# Ambient_Board_v1_1b.net
KiCad netlist of a schematic drawn in EAGLE
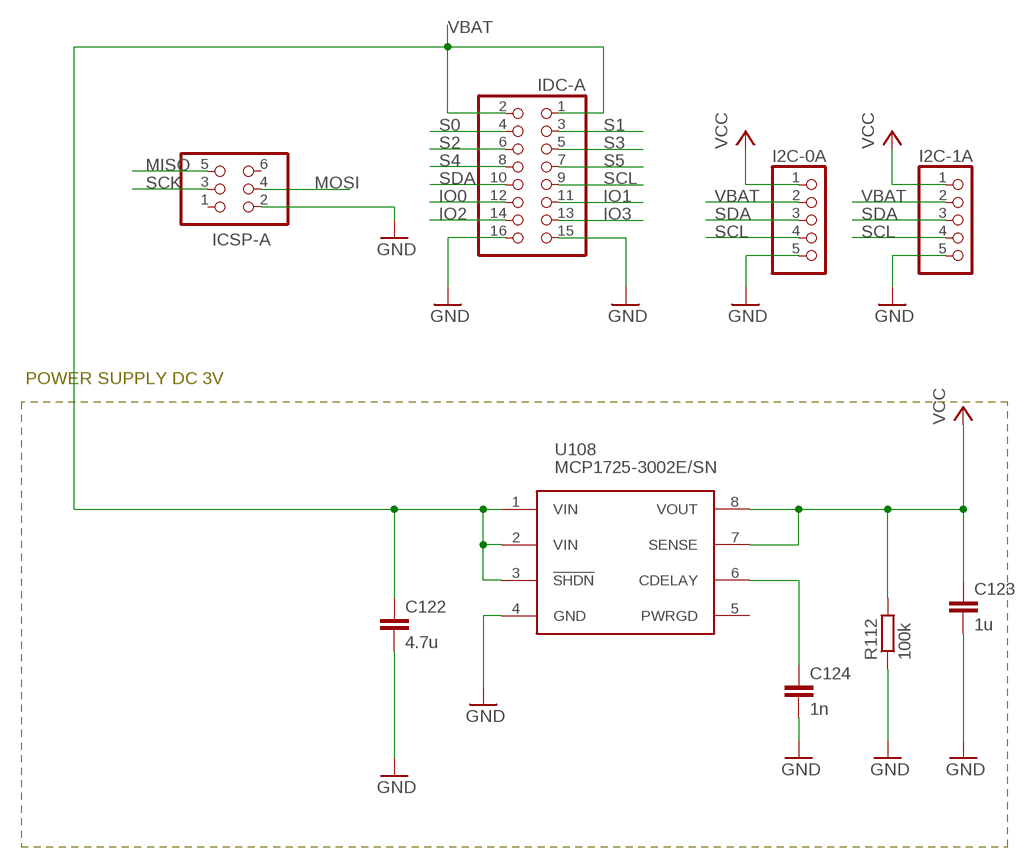
[diagram p0: schematic, sheet 1]
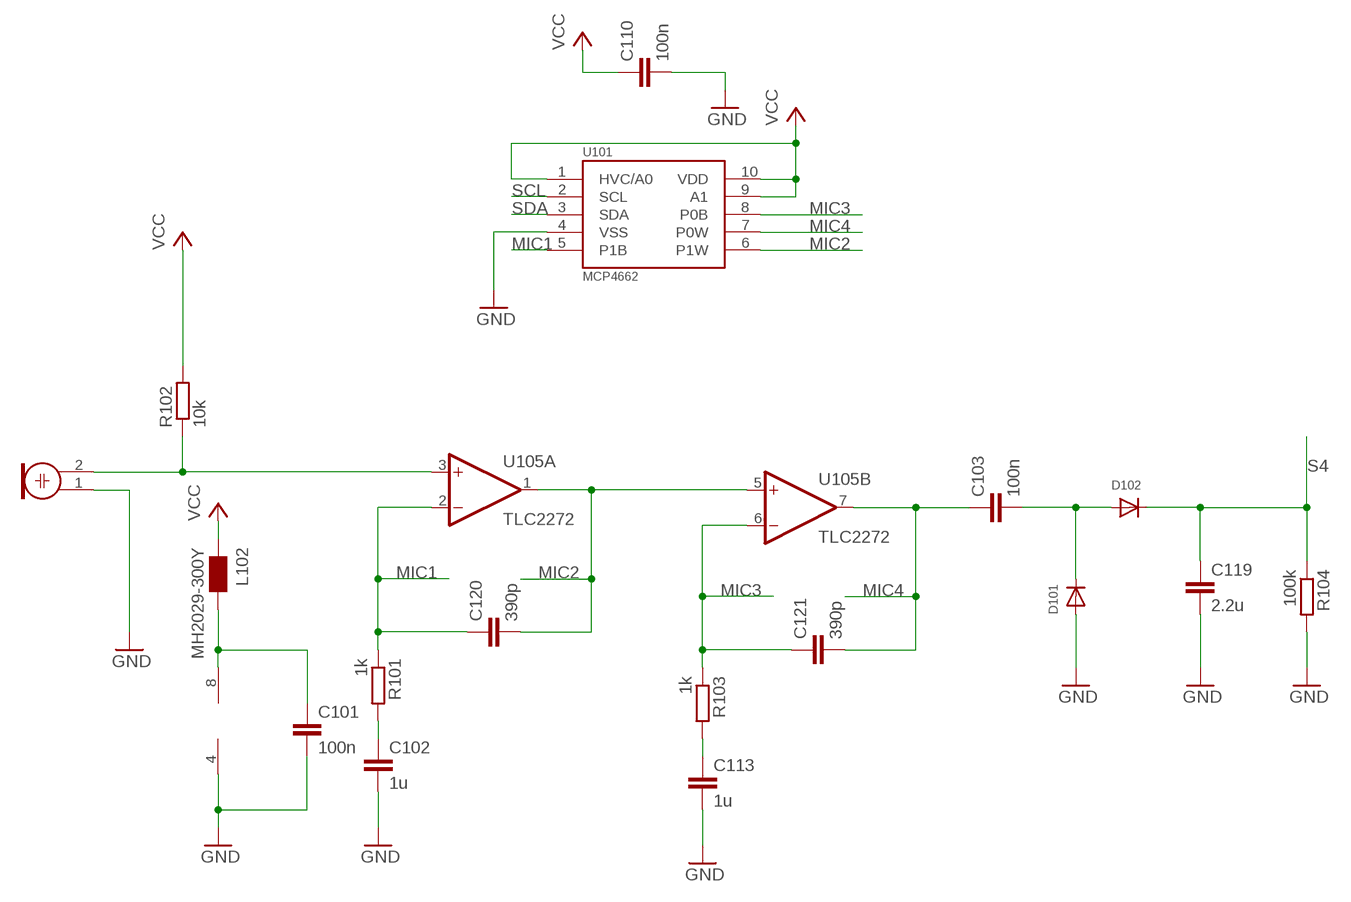
[diagram p1: schematic, sheet 2]
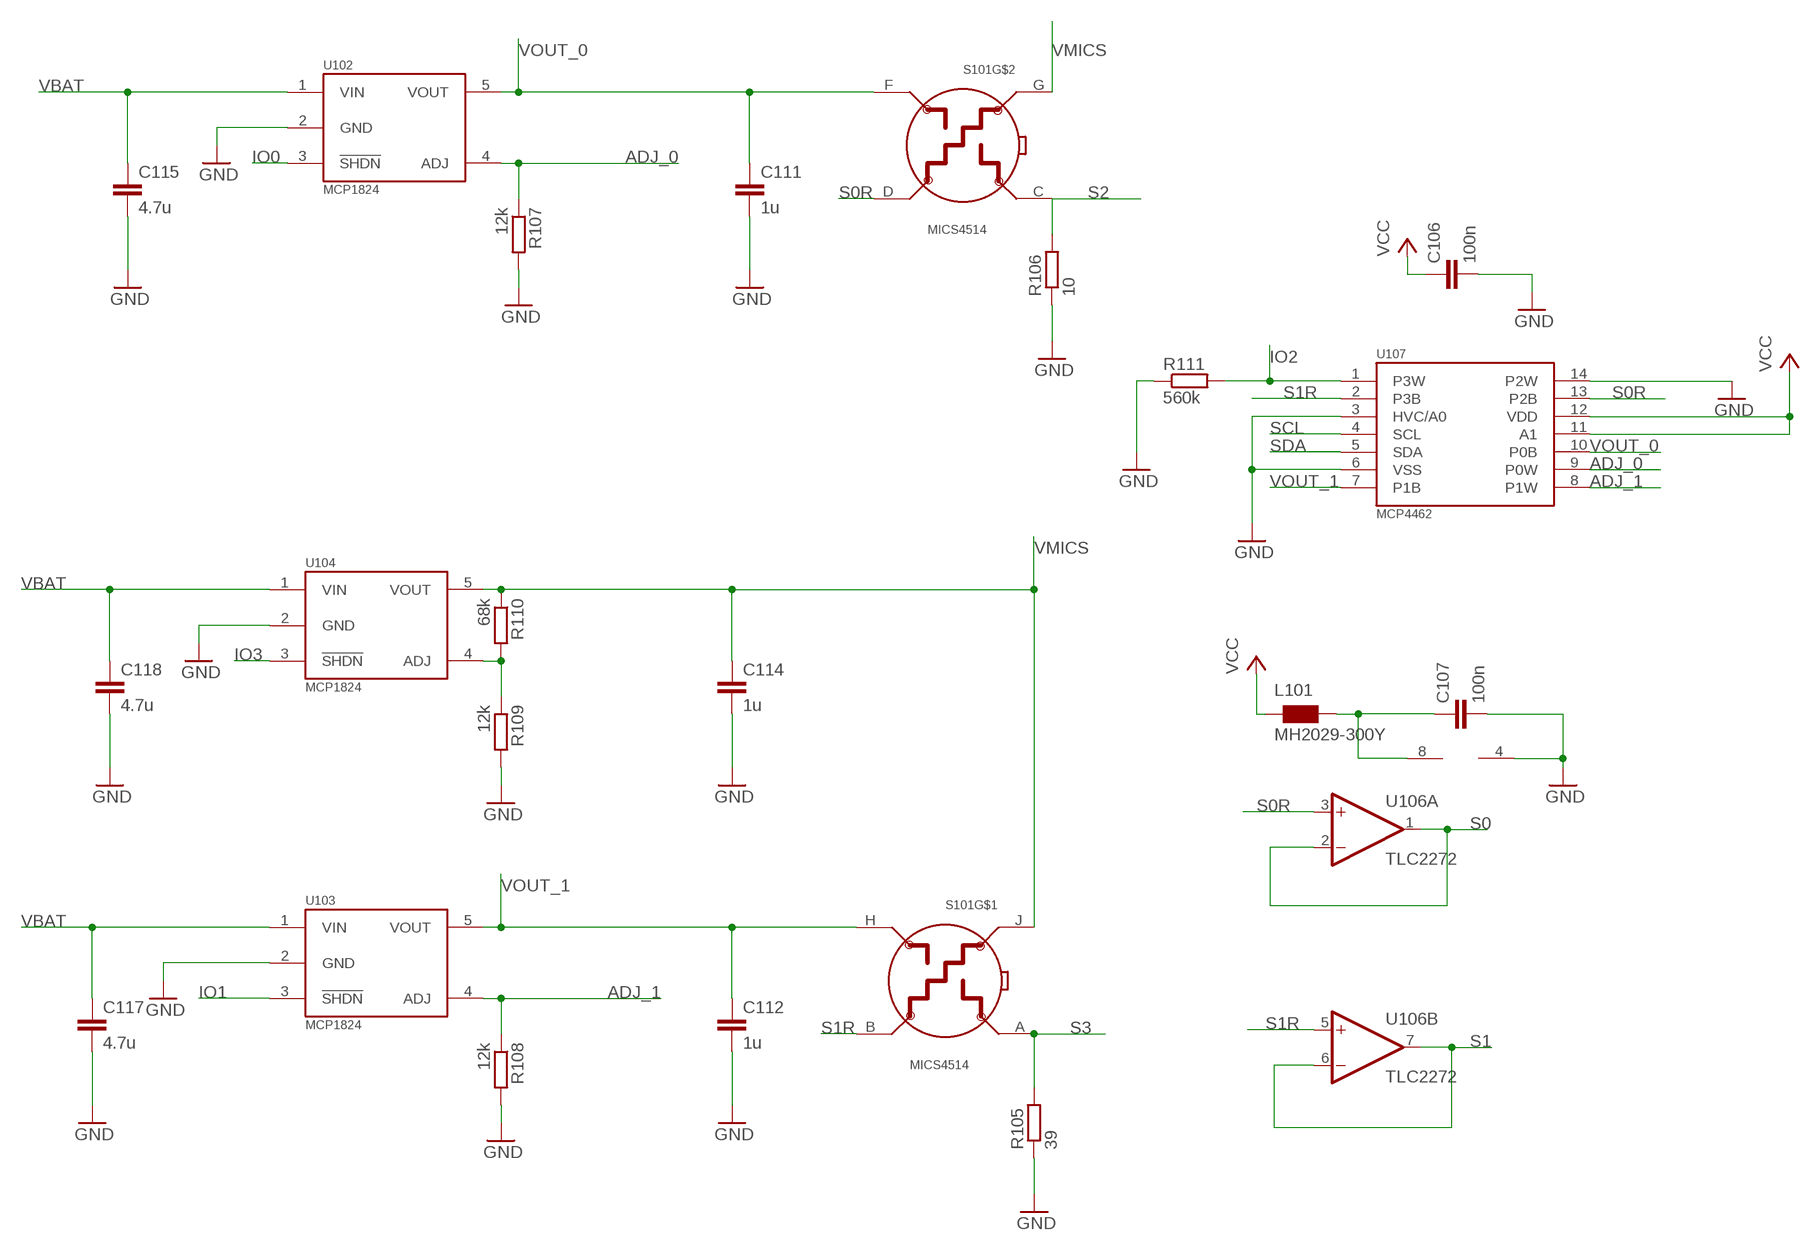
[diagram p2: schematic, sheet 3]
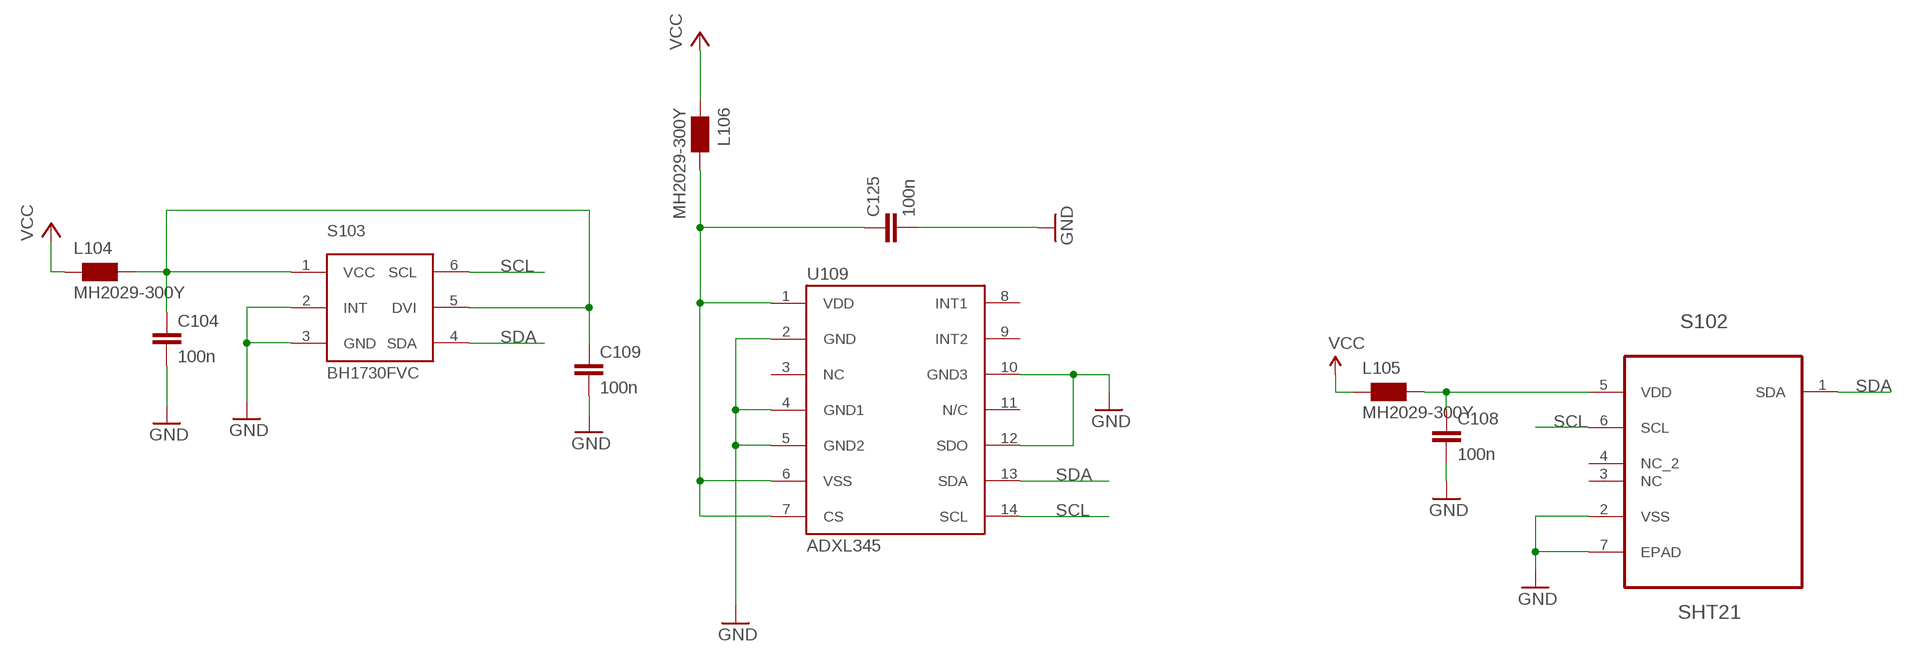
[diagram p3: schematic, sheet 4]

(export (version "E")
  (design (tool "Eeschema 10.0.6"))
  (components
    (comp (ref "C106")
      (value "100n")
      (footprint "eagle-import:C0603")
      (libsource (lib "eagle-import") (part "C-EUC0603"))
    )
    (comp (ref "C107")
      (value "100n")
      (footprint "eagle-import:C0603")
      (libsource (lib "eagle-import") (part "C-EUC0603"))
    )
    (comp (ref "C111")
      (value "1u")
      (footprint "eagle-import:C0805")
      (libsource (lib "eagle-import") (part "C-EUC0805"))
    )
    (comp (ref "C112")
      (value "1u")
      (footprint "eagle-import:C0805")
      (libsource (lib "eagle-import") (part "C-EUC0805"))
    )
    (comp (ref "C114")
      (value "1u")
      (footprint "eagle-import:C0805")
      (libsource (lib "eagle-import") (part "C-EUC0805"))
    )
    (comp (ref "C115")
      (value "4.7u")
      (footprint "eagle-import:C0805")
      (libsource (lib "eagle-import") (part "C-EUC0805"))
    )
    (comp (ref "C117")
      (value "4.7u")
      (footprint "eagle-import:C0805")
      (libsource (lib "eagle-import") (part "C-EUC0805"))
    )
    (comp (ref "C118")
      (value "4.7u")
      (footprint "eagle-import:C0805")
      (libsource (lib "eagle-import") (part "C-EUC0805"))
    )
    (comp (ref "L101")
      (value "MH2029-300Y")
      (footprint "eagle-import:0805")
      (libsource (lib "eagle-import") (part "WE-CBF_0805"))
    )
    (comp (ref "R105")
      (value "39")
      (footprint "eagle-import:R0603")
      (libsource (lib "eagle-import") (part "R-EU_R0603"))
    )
    (comp (ref "R106")
      (value "10")
      (footprint "eagle-import:R0603")
      (libsource (lib "eagle-import") (part "R-EU_R0603"))
    )
    (comp (ref "R107")
      (value "12k")
      (footprint "eagle-import:R0603")
      (libsource (lib "eagle-import") (part "R-EU_R0603"))
    )
    (comp (ref "R108")
      (value "12k")
      (footprint "eagle-import:R0603")
      (libsource (lib "eagle-import") (part "R-EU_R0603"))
    )
    (comp (ref "R109")
      (value "12k")
      (footprint "eagle-import:R0603")
      (libsource (lib "eagle-import") (part "R-EU_R0603"))
    )
    (comp (ref "R110")
      (value "68k")
      (footprint "eagle-import:R0603")
      (libsource (lib "eagle-import") (part "R-EU_R0603"))
    )
    (comp (ref "R111")
      (value "560k")
      (footprint "eagle-import:R0603")
      (libsource (lib "eagle-import") (part "R-EU_R0603"))
    )
    (comp (ref "S101")
      (value "MICS4514")
      (footprint "eagle-import:MICS_SMD")
      (libsource (lib "eagle-import") (part "MICS4514"))
    )
    (comp (ref "U102")
      (value "MCP1824")
      (footprint "eagle-import:SOT23-5L")
      (libsource (lib "eagle-import") (part "TC1071"))
    )
    (comp (ref "U103")
      (value "MCP1824")
      (footprint "eagle-import:SOT23-5L")
      (libsource (lib "eagle-import") (part "TC1071"))
    )
    (comp (ref "U104")
      (value "MCP1824")
      (footprint "eagle-import:SOT23-5L")
      (libsource (lib "eagle-import") (part "TC1071"))
    )
    (comp (ref "U106")
      (value "TLC2272")
      (footprint "eagle-import:SO08")
      (libsource (lib "eagle-import") (part "TL082D"))
    )
    (comp (ref "U107")
      (value "MCP4462")
      (footprint "eagle-import:TSSOP14")
      (libsource (lib "eagle-import") (part "MCP4462"))
    )
    (comp (ref "C122")
      (value "4.7u")
      (footprint "eagle-import:C0805")
      (libsource (lib "eagle-import") (part "C-EUC0805"))
    )
    (comp (ref "C123")
      (value "1u")
      (footprint "eagle-import:C0805")
      (libsource (lib "eagle-import") (part "C-EUC0805"))
    )
    (comp (ref "C124")
      (value "1n")
      (footprint "eagle-import:C0603K")
      (libsource (lib "eagle-import") (part "C-EUC0603K"))
    )
    (comp (ref "I2C-0A")
      (value "PINHD-1X5")
      (footprint "eagle-import:1X05")
      (libsource (lib "eagle-import") (part "PINHD-1X5"))
    )
    (comp (ref "I2C-1A")
      (value "PINHD-1X5")
      (footprint "eagle-import:1X05")
      (libsource (lib "eagle-import") (part "PINHD-1X5"))
    )
    (comp (ref "ICSP-A")
      (value "ICSP-A")
      (footprint "eagle-import:2X03")
      (libsource (lib "eagle-import") (part "PINHD-2X3"))
    )
    (comp (ref "IDC-A")
      (value "PINHD-2X8")
      (footprint "eagle-import:2X08")
      (libsource (lib "eagle-import") (part "PINHD-2X8"))
    )
    (comp (ref "R112")
      (value "100k")
      (footprint "eagle-import:R0603")
      (libsource (lib "eagle-import") (part "R-EU_R0603"))
    )
    (comp (ref "U108")
      (value "MCP1725-3002E/SN")
      (footprint "eagle-import:SOIC8")
      (libsource (lib "eagle-import") (part "MCP1725"))
    )
    (comp (ref "C101")
      (value "100n")
      (footprint "eagle-import:C0603")
      (libsource (lib "eagle-import") (part "C-EUC0603"))
    )
    (comp (ref "C102")
      (value "1u")
      (footprint "eagle-import:C0805")
      (libsource (lib "eagle-import") (part "C-EUC0805"))
    )
    (comp (ref "C103")
      (value "100n")
      (footprint "eagle-import:C0603")
      (libsource (lib "eagle-import") (part "C-EUC0603"))
    )
    (comp (ref "C110")
      (value "100n")
      (footprint "eagle-import:C0603")
      (libsource (lib "eagle-import") (part "C-EUC0603"))
    )
    (comp (ref "C113")
      (value "1u")
      (footprint "eagle-import:C0805")
      (libsource (lib "eagle-import") (part "C-EUC0805"))
    )
    (comp (ref "C119")
      (value "2.2u")
      (footprint "eagle-import:C0805")
      (libsource (lib "eagle-import") (part "C-EUC0805"))
    )
    (comp (ref "C120")
      (value "390p")
      (footprint "eagle-import:C0603")
      (libsource (lib "eagle-import") (part "C-EUC0603"))
    )
    (comp (ref "C121")
      (value "390p")
      (footprint "eagle-import:C0603")
      (libsource (lib "eagle-import") (part "C-EUC0603"))
    )
    (comp (ref "D101")
      (value "DIODESOD-323F")
      (footprint "eagle-import:SOD-323F")
      (libsource (lib "eagle-import") (part "DIODESOD-323F"))
    )
    (comp (ref "D102")
      (value "DIODESOD-323F")
      (footprint "eagle-import:SOD-323F")
      (libsource (lib "eagle-import") (part "DIODESOD-323F"))
    )
    (comp (ref "L102")
      (value "MH2029-300Y")
      (footprint "eagle-import:0805")
      (libsource (lib "eagle-import") (part "WE-CBF_0805"))
    )
    (comp (ref "M101")
      (value "POM-3044P-R")
      (footprint "eagle-import:WM-63PR")
      (libsource (lib "eagle-import") (part "ELECTRET_MICROPHON-WM-63PR"))
    )
    (comp (ref "R101")
      (value "1k")
      (footprint "eagle-import:R0603")
      (libsource (lib "eagle-import") (part "R-EU_R0603"))
    )
    (comp (ref "R102")
      (value "10k")
      (footprint "eagle-import:R0603")
      (libsource (lib "eagle-import") (part "R-EU_R0603"))
    )
    (comp (ref "R103")
      (value "1k")
      (footprint "eagle-import:R0603")
      (libsource (lib "eagle-import") (part "R-EU_R0603"))
    )
    (comp (ref "R104")
      (value "100k")
      (footprint "eagle-import:R0603")
      (libsource (lib "eagle-import") (part "R-EU_R0603"))
    )
    (comp (ref "U101")
      (value "MCP4662")
      (footprint "eagle-import:MSOP10")
      (libsource (lib "eagle-import") (part "MCP4662"))
    )
    (comp (ref "U105")
      (value "TLC2272")
      (footprint "eagle-import:SO08")
      (libsource (lib "eagle-import") (part "TL082D"))
    )
    (comp (ref "C104")
      (value "100n")
      (footprint "eagle-import:C0603")
      (libsource (lib "eagle-import") (part "C-EUC0603"))
    )
    (comp (ref "C108")
      (value "100n")
      (footprint "eagle-import:C0603")
      (libsource (lib "eagle-import") (part "C-EUC0603"))
    )
    (comp (ref "C109")
      (value "100n")
      (footprint "eagle-import:C0603")
      (libsource (lib "eagle-import") (part "C-EUC0603"))
    )
    (comp (ref "C125")
      (value "100n")
      (footprint "eagle-import:C0603")
      (libsource (lib "eagle-import") (part "C-EUC0603"))
    )
    (comp (ref "L104")
      (value "MH2029-300Y")
      (footprint "eagle-import:0805")
      (libsource (lib "eagle-import") (part "WE-CBF_0805"))
    )
    (comp (ref "L105")
      (value "MH2029-300Y")
      (footprint "eagle-import:0805")
      (libsource (lib "eagle-import") (part "WE-CBF_0805"))
    )
    (comp (ref "L106")
      (value "MH2029-300Y")
      (footprint "eagle-import:0805")
      (libsource (lib "eagle-import") (part "WE-CBF_0805"))
    )
    (comp (ref "S102")
      (value "SHT21")
      (footprint "eagle-import:DFN300X300X110-7N")
      (libsource (lib "eagle-import") (part "SHT21"))
    )
    (comp (ref "S103")
      (value "BH1730FVC")
      (footprint "eagle-import:WSOF6")
      (libsource (lib "eagle-import") (part "BH1730FVC"))
    )
    (comp (ref "U109")
      (value "ADXL345")
      (footprint "eagle-import:LGA14")
      (libsource (lib "eagle-import") (part "ADXL345"))
    )
  )
  (nets
    (net (code "1") (name "ADJ_0") (class "Default")
      (node (ref "R107") (pin "1") (pinfunction "1_1") (pintype "passive"))
      (node (ref "U102") (pin "4") (pinfunction "ADJ_4") (pintype "bidirectional"))
      (node (ref "U107") (pin "9") (pinfunction "P0W_9") (pintype "bidirectional"))
    )
    (net (code "2") (name "ADJ_1") (class "Default")
      (node (ref "R108") (pin "1") (pinfunction "1_1") (pintype "passive"))
      (node (ref "U103") (pin "4") (pinfunction "ADJ_4") (pintype "bidirectional"))
      (node (ref "U107") (pin "8") (pinfunction "P1W_8") (pintype "bidirectional"))
    )
    (net (code "3") (name "GND") (class "Default")
      (node (ref "C101") (pin "2") (pinfunction "2_2") (pintype "passive"))
      (node (ref "C102") (pin "2") (pinfunction "2_2") (pintype "passive"))
      (node (ref "C104") (pin "2") (pinfunction "2_2") (pintype "passive"))
      (node (ref "C106") (pin "2") (pinfunction "2_2") (pintype "passive"))
      (node (ref "C107") (pin "2") (pinfunction "2_2") (pintype "passive"))
      (node (ref "C108") (pin "2") (pinfunction "2_2") (pintype "passive"))
      (node (ref "C109") (pin "2") (pinfunction "2_2") (pintype "passive"))
      (node (ref "C110") (pin "2") (pinfunction "2_2") (pintype "passive"))
      (node (ref "C111") (pin "2") (pinfunction "2_2") (pintype "passive"))
      (node (ref "C112") (pin "2") (pinfunction "2_2") (pintype "passive"))
      (node (ref "C113") (pin "2") (pinfunction "2_2") (pintype "passive"))
      (node (ref "C114") (pin "2") (pinfunction "2_2") (pintype "passive"))
      (node (ref "C115") (pin "2") (pinfunction "2_2") (pintype "passive"))
      (node (ref "C117") (pin "2") (pinfunction "2_2") (pintype "passive"))
      (node (ref "C118") (pin "2") (pinfunction "2_2") (pintype "passive"))
      (node (ref "C119") (pin "2") (pinfunction "2_2") (pintype "passive"))
      (node (ref "C122") (pin "2") (pinfunction "2_2") (pintype "passive"))
      (node (ref "C123") (pin "2") (pinfunction "2_2") (pintype "passive"))
      (node (ref "C124") (pin "2") (pinfunction "2_2") (pintype "passive"))
      (node (ref "C125") (pin "2") (pinfunction "2_2") (pintype "passive"))
      (node (ref "D101") (pin "A") (pinfunction "A_A") (pintype "passive"))
      (node (ref "I2C-0A") (pin "5") (pinfunction "5_5") (pintype "passive"))
      (node (ref "I2C-1A") (pin "5") (pinfunction "5_5") (pintype "passive"))
      (node (ref "ICSP-A") (pin "2") (pinfunction "2_2") (pintype "passive"))
      (node (ref "IDC-A") (pin "15") (pinfunction "15_15") (pintype "passive"))
      (node (ref "IDC-A") (pin "16") (pinfunction "16_16") (pintype "passive"))
      (node (ref "M101") (pin "1") (pinfunction "1_1") (pintype "passive"))
      (node (ref "R104") (pin "2") (pinfunction "2_2") (pintype "passive"))
      (node (ref "R105") (pin "1") (pinfunction "1_1") (pintype "passive"))
      (node (ref "R106") (pin "1") (pinfunction "1_1") (pintype "passive"))
      (node (ref "R107") (pin "2") (pinfunction "2_2") (pintype "passive"))
      (node (ref "R108") (pin "2") (pinfunction "2_2") (pintype "passive"))
      (node (ref "R109") (pin "2") (pinfunction "2_2") (pintype "passive"))
      (node (ref "R111") (pin "1") (pinfunction "1_1") (pintype "passive"))
      (node (ref "R112") (pin "1") (pinfunction "1_1") (pintype "passive"))
      (node (ref "S102") (pin "2") (pinfunction "VSS_2") (pintype "power_in"))
      (node (ref "S102") (pin "7") (pinfunction "EPAD_7") (pintype "passive"))
      (node (ref "S103") (pin "2") (pinfunction "INT_2") (pintype "bidirectional"))
      (node (ref "S103") (pin "3") (pinfunction "GND_3") (pintype "bidirectional"))
      (node (ref "U101") (pin "4") (pinfunction "VSS_4") (pintype "bidirectional"))
      (node (ref "U102") (pin "2") (pinfunction "GND_2") (pintype "bidirectional"))
      (node (ref "U103") (pin "2") (pinfunction "GND_2") (pintype "bidirectional"))
      (node (ref "U104") (pin "2") (pinfunction "GND_2") (pintype "bidirectional"))
      (node (ref "U105") (pin "4") (pinfunction "V-_4") (pintype "power_in"))
      (node (ref "U106") (pin "4") (pinfunction "V-_4") (pintype "power_in"))
      (node (ref "U107") (pin "14") (pinfunction "P2W_14") (pintype "bidirectional"))
      (node (ref "U107") (pin "3") (pinfunction "HVC/A0_3") (pintype "bidirectional"))
      (node (ref "U107") (pin "6") (pinfunction "VSS_6") (pintype "bidirectional"))
      (node (ref "U108") (pin "4") (pinfunction "GND_4") (pintype "bidirectional"))
      (node (ref "U109") (pin "10") (pinfunction "GND3_10") (pintype "bidirectional"))
      (node (ref "U109") (pin "12") (pinfunction "SDO_12") (pintype "bidirectional"))
      (node (ref "U109") (pin "2") (pinfunction "GND_2") (pintype "bidirectional"))
      (node (ref "U109") (pin "4") (pinfunction "GND1_4") (pintype "bidirectional"))
      (node (ref "U109") (pin "5") (pinfunction "GND2_5") (pintype "bidirectional"))
    )
    (net (code "4") (name "IO0") (class "Default")
      (node (ref "IDC-A") (pin "12") (pinfunction "12_12") (pintype "passive"))
      (node (ref "U102") (pin "3") (pinfunction "~{SHDN}_3") (pintype "bidirectional"))
    )
    (net (code "5") (name "IO1") (class "Default")
      (node (ref "IDC-A") (pin "11") (pinfunction "11_11") (pintype "passive"))
      (node (ref "U103") (pin "3") (pinfunction "~{SHDN}_3") (pintype "bidirectional"))
    )
    (net (code "6") (name "IO2") (class "Default")
      (node (ref "IDC-A") (pin "14") (pinfunction "14_14") (pintype "passive"))
      (node (ref "R111") (pin "2") (pinfunction "2_2") (pintype "passive"))
      (node (ref "U107") (pin "1") (pinfunction "P3W_1") (pintype "bidirectional"))
    )
    (net (code "7") (name "IO3") (class "Default")
      (node (ref "IDC-A") (pin "13") (pinfunction "13_13") (pintype "passive"))
      (node (ref "U104") (pin "3") (pinfunction "~{SHDN}_3") (pintype "bidirectional"))
    )
    (net (code "8") (name "MIC1") (class "Default")
      (node (ref "C120") (pin "1") (pinfunction "1_1") (pintype "passive"))
      (node (ref "R101") (pin "1") (pinfunction "1_1") (pintype "passive"))
      (node (ref "U101") (pin "5") (pinfunction "P1B_5") (pintype "bidirectional"))
      (node (ref "U105") (pin "2") (pinfunction "-IN_2") (pintype "input"))
    )
    (net (code "9") (name "MIC2") (class "Default")
      (node (ref "C120") (pin "2") (pinfunction "2_2") (pintype "passive"))
      (node (ref "U101") (pin "6") (pinfunction "P1W_6") (pintype "bidirectional"))
      (node (ref "U105") (pin "1") (pinfunction "OUT_1") (pintype "output"))
      (node (ref "U105") (pin "5") (pinfunction "+IN_5") (pintype "input"))
    )
    (net (code "10") (name "MIC3") (class "Default")
      (node (ref "C121") (pin "1") (pinfunction "1_1") (pintype "passive"))
      (node (ref "R103") (pin "1") (pinfunction "1_1") (pintype "passive"))
      (node (ref "U101") (pin "8") (pinfunction "P0B_8") (pintype "bidirectional"))
      (node (ref "U105") (pin "6") (pinfunction "-IN_6") (pintype "input"))
    )
    (net (code "11") (name "MIC4") (class "Default")
      (node (ref "C103") (pin "1") (pinfunction "1_1") (pintype "passive"))
      (node (ref "C121") (pin "2") (pinfunction "2_2") (pintype "passive"))
      (node (ref "U101") (pin "7") (pinfunction "P0W_7") (pintype "bidirectional"))
      (node (ref "U105") (pin "7") (pinfunction "OUT_7") (pintype "output"))
    )
    (net (code "12") (name "MISO") (class "Default")
      (node (ref "ICSP-A") (pin "5") (pinfunction "5_5") (pintype "passive"))
    )
    (net (code "13") (name "MOSI") (class "Default")
      (node (ref "ICSP-A") (pin "4") (pinfunction "4_4") (pintype "passive"))
    )
    (net (code "14") (name "Net-(C102-Pad1)") (class "Default")
      (node (ref "C102") (pin "1") (pinfunction "1_1") (pintype "passive"))
      (node (ref "R101") (pin "2") (pinfunction "2_2") (pintype "passive"))
    )
    (net (code "15") (name "Net-(C103-Pad2)") (class "Default")
      (node (ref "C103") (pin "2") (pinfunction "2_2") (pintype "passive"))
      (node (ref "D101") (pin "C") (pinfunction "C_C") (pintype "passive"))
      (node (ref "D102") (pin "A") (pinfunction "A_A") (pintype "passive"))
    )
    (net (code "16") (name "Net-(C113-Pad1)") (class "Default")
      (node (ref "C113") (pin "1") (pinfunction "1_1") (pintype "passive"))
      (node (ref "R103") (pin "2") (pinfunction "2_2") (pintype "passive"))
    )
    (net (code "17") (name "Net-(S102-VDD)") (class "Default")
      (node (ref "C108") (pin "1") (pinfunction "1_1") (pintype "passive"))
      (node (ref "L105") (pin "2") (pinfunction "2_2") (pintype "passive"))
      (node (ref "S102") (pin "5") (pinfunction "VDD_5") (pintype "power_in"))
    )
    (net (code "18") (name "Net-(S103-DVI)") (class "Default")
      (node (ref "C104") (pin "1") (pinfunction "1_1") (pintype "passive"))
      (node (ref "C109") (pin "1") (pinfunction "1_1") (pintype "passive"))
      (node (ref "L104") (pin "2") (pinfunction "2_2") (pintype "passive"))
      (node (ref "S103") (pin "1") (pinfunction "VCC_1") (pintype "bidirectional"))
      (node (ref "S103") (pin "5") (pinfunction "DVI_5") (pintype "bidirectional"))
    )
    (net (code "19") (name "Net-(U104-ADJ)") (class "Default")
      (node (ref "R109") (pin "1") (pinfunction "1_1") (pintype "passive"))
      (node (ref "R110") (pin "2") (pinfunction "2_2") (pintype "passive"))
      (node (ref "U104") (pin "4") (pinfunction "ADJ_4") (pintype "bidirectional"))
    )
    (net (code "20") (name "Net-(U105A-+IN)") (class "Default")
      (node (ref "M101") (pin "2") (pinfunction "2_2") (pintype "passive"))
      (node (ref "R102") (pin "1") (pinfunction "1_1") (pintype "passive"))
      (node (ref "U105") (pin "3") (pinfunction "+IN_3") (pintype "input"))
    )
    (net (code "21") (name "Net-(U105C-V+)") (class "Default")
      (node (ref "C101") (pin "1") (pinfunction "1_1") (pintype "passive"))
      (node (ref "L102") (pin "2") (pinfunction "2_2") (pintype "passive"))
      (node (ref "U105") (pin "8") (pinfunction "V+_8") (pintype "power_in"))
    )
    (net (code "22") (name "Net-(U106C-V+)") (class "Default")
      (node (ref "C107") (pin "1") (pinfunction "1_1") (pintype "passive"))
      (node (ref "L101") (pin "2") (pinfunction "2_2") (pintype "passive"))
      (node (ref "U106") (pin "8") (pinfunction "V+_8") (pintype "power_in"))
    )
    (net (code "23") (name "Net-(U108-CDELAY)") (class "Default")
      (node (ref "C124") (pin "1") (pinfunction "1_1") (pintype "passive"))
      (node (ref "U108") (pin "6") (pinfunction "CDELAY_6") (pintype "bidirectional"))
    )
    (net (code "24") (name "Net-(U109-CS)") (class "Default")
      (node (ref "C125") (pin "1") (pinfunction "1_1") (pintype "passive"))
      (node (ref "L106") (pin "2") (pinfunction "2_2") (pintype "passive"))
      (node (ref "U109") (pin "1") (pinfunction "VDD_1") (pintype "bidirectional"))
      (node (ref "U109") (pin "6") (pinfunction "VSS_6") (pintype "bidirectional"))
      (node (ref "U109") (pin "7") (pinfunction "CS_7") (pintype "bidirectional"))
    )
    (net (code "25") (name "S0") (class "Default")
      (node (ref "IDC-A") (pin "4") (pinfunction "4_4") (pintype "passive"))
      (node (ref "U106") (pin "1") (pinfunction "OUT_1") (pintype "output"))
      (node (ref "U106") (pin "2") (pinfunction "-IN_2") (pintype "input"))
    )
    (net (code "26") (name "S0R") (class "Default")
      (node (ref "S101") (pin "D") (pinfunction "4_D") (pintype "bidirectional"))
      (node (ref "U106") (pin "3") (pinfunction "+IN_3") (pintype "input"))
      (node (ref "U107") (pin "13") (pinfunction "P2B_13") (pintype "bidirectional"))
    )
    (net (code "27") (name "S1") (class "Default")
      (node (ref "IDC-A") (pin "3") (pinfunction "3_3") (pintype "passive"))
      (node (ref "U106") (pin "6") (pinfunction "-IN_6") (pintype "input"))
      (node (ref "U106") (pin "7") (pinfunction "OUT_7") (pintype "output"))
    )
    (net (code "28") (name "S1R") (class "Default")
      (node (ref "S101") (pin "B") (pinfunction "4_B") (pintype "bidirectional"))
      (node (ref "U106") (pin "5") (pinfunction "+IN_5") (pintype "input"))
      (node (ref "U107") (pin "2") (pinfunction "P3B_2") (pintype "bidirectional"))
    )
    (net (code "29") (name "S2") (class "Default")
      (node (ref "IDC-A") (pin "6") (pinfunction "6_6") (pintype "passive"))
      (node (ref "R106") (pin "2") (pinfunction "2_2") (pintype "passive"))
      (node (ref "S101") (pin "C") (pinfunction "1_C") (pintype "bidirectional"))
    )
    (net (code "30") (name "S3") (class "Default")
      (node (ref "IDC-A") (pin "5") (pinfunction "5_5") (pintype "passive"))
      (node (ref "R105") (pin "2") (pinfunction "2_2") (pintype "passive"))
      (node (ref "S101") (pin "A") (pinfunction "1_A") (pintype "bidirectional"))
    )
    (net (code "31") (name "S4") (class "Default")
      (node (ref "C119") (pin "1") (pinfunction "1_1") (pintype "passive"))
      (node (ref "D102") (pin "C") (pinfunction "C_C") (pintype "passive"))
      (node (ref "IDC-A") (pin "8") (pinfunction "8_8") (pintype "passive"))
      (node (ref "R104") (pin "1") (pinfunction "1_1") (pintype "passive"))
    )
    (net (code "32") (name "S5") (class "Default")
      (node (ref "IDC-A") (pin "7") (pinfunction "7_7") (pintype "passive"))
    )
    (net (code "33") (name "SCK") (class "Default")
      (node (ref "ICSP-A") (pin "3") (pinfunction "3_3") (pintype "passive"))
    )
    (net (code "34") (name "SCL") (class "Default")
      (node (ref "I2C-0A") (pin "4") (pinfunction "4_4") (pintype "passive"))
      (node (ref "I2C-1A") (pin "4") (pinfunction "4_4") (pintype "passive"))
      (node (ref "IDC-A") (pin "9") (pinfunction "9_9") (pintype "passive"))
      (node (ref "S102") (pin "6") (pinfunction "SCL_6") (pintype "input"))
      (node (ref "S103") (pin "6") (pinfunction "SCL_6") (pintype "bidirectional"))
      (node (ref "U101") (pin "2") (pinfunction "SCL_2") (pintype "bidirectional"))
      (node (ref "U107") (pin "4") (pinfunction "SCL_4") (pintype "bidirectional"))
      (node (ref "U109") (pin "14") (pinfunction "SCL_14") (pintype "bidirectional"))
    )
    (net (code "35") (name "SDA") (class "Default")
      (node (ref "I2C-0A") (pin "3") (pinfunction "3_3") (pintype "passive"))
      (node (ref "I2C-1A") (pin "3") (pinfunction "3_3") (pintype "passive"))
      (node (ref "IDC-A") (pin "10") (pinfunction "10_10") (pintype "passive"))
      (node (ref "S102") (pin "1") (pinfunction "SDA_1") (pintype "bidirectional"))
      (node (ref "S103") (pin "4") (pinfunction "SDA_4") (pintype "bidirectional"))
      (node (ref "U101") (pin "3") (pinfunction "SDA_3") (pintype "bidirectional"))
      (node (ref "U107") (pin "5") (pinfunction "SDA_5") (pintype "bidirectional"))
      (node (ref "U109") (pin "13") (pinfunction "SDA_13") (pintype "bidirectional"))
    )
    (net (code "36") (name "VBAT") (class "Default")
      (node (ref "C115") (pin "1") (pinfunction "1_1") (pintype "passive"))
      (node (ref "C117") (pin "1") (pinfunction "1_1") (pintype "passive"))
      (node (ref "C118") (pin "1") (pinfunction "1_1") (pintype "passive"))
      (node (ref "C122") (pin "1") (pinfunction "1_1") (pintype "passive"))
      (node (ref "I2C-0A") (pin "2") (pinfunction "2_2") (pintype "passive"))
      (node (ref "I2C-1A") (pin "2") (pinfunction "2_2") (pintype "passive"))
      (node (ref "IDC-A") (pin "1") (pinfunction "1_1") (pintype "passive"))
      (node (ref "IDC-A") (pin "2") (pinfunction "2_2") (pintype "passive"))
      (node (ref "U102") (pin "1") (pinfunction "VIN_1") (pintype "bidirectional"))
      (node (ref "U103") (pin "1") (pinfunction "VIN_1") (pintype "bidirectional"))
      (node (ref "U104") (pin "1") (pinfunction "VIN_1") (pintype "bidirectional"))
      (node (ref "U108") (pin "1") (pinfunction "VIN_1") (pintype "bidirectional"))
      (node (ref "U108") (pin "2") (pinfunction "VIN_2") (pintype "bidirectional"))
      (node (ref "U108") (pin "3") (pinfunction "~{SHDN}_3") (pintype "bidirectional"))
    )
    (net (code "37") (name "VCC") (class "Default")
      (node (ref "C106") (pin "1") (pinfunction "1_1") (pintype "passive"))
      (node (ref "C110") (pin "1") (pinfunction "1_1") (pintype "passive"))
      (node (ref "C123") (pin "1") (pinfunction "1_1") (pintype "passive"))
      (node (ref "I2C-0A") (pin "1") (pinfunction "1_1") (pintype "passive"))
      (node (ref "I2C-1A") (pin "1") (pinfunction "1_1") (pintype "passive"))
      (node (ref "L101") (pin "1") (pinfunction "1_1") (pintype "passive"))
      (node (ref "L102") (pin "1") (pinfunction "1_1") (pintype "passive"))
      (node (ref "L104") (pin "1") (pinfunction "1_1") (pintype "passive"))
      (node (ref "L105") (pin "1") (pinfunction "1_1") (pintype "passive"))
      (node (ref "L106") (pin "1") (pinfunction "1_1") (pintype "passive"))
      (node (ref "R102") (pin "2") (pinfunction "2_2") (pintype "passive"))
      (node (ref "R112") (pin "2") (pinfunction "2_2") (pintype "passive"))
      (node (ref "U101") (pin "1") (pinfunction "HVC/A0_1") (pintype "bidirectional"))
      (node (ref "U101") (pin "10") (pinfunction "VDD_10") (pintype "bidirectional"))
      (node (ref "U101") (pin "9") (pinfunction "A1_9") (pintype "bidirectional"))
      (node (ref "U107") (pin "11") (pinfunction "A1_11") (pintype "bidirectional"))
      (node (ref "U107") (pin "12") (pinfunction "VDD_12") (pintype "bidirectional"))
      (node (ref "U108") (pin "7") (pinfunction "SENSE_7") (pintype "bidirectional"))
      (node (ref "U108") (pin "8") (pinfunction "VOUT_8") (pintype "bidirectional"))
    )
    (net (code "38") (name "VMICS") (class "Default")
      (node (ref "C114") (pin "1") (pinfunction "1_1") (pintype "passive"))
      (node (ref "R110") (pin "1") (pinfunction "1_1") (pintype "passive"))
      (node (ref "S101") (pin "G") (pinfunction "2_G") (pintype "bidirectional"))
      (node (ref "S101") (pin "J") (pinfunction "2_J") (pintype "bidirectional"))
      (node (ref "U104") (pin "5") (pinfunction "VOUT_5") (pintype "bidirectional"))
    )
    (net (code "39") (name "VOUT_0") (class "Default")
      (node (ref "C111") (pin "1") (pinfunction "1_1") (pintype "passive"))
      (node (ref "S101") (pin "F") (pinfunction "3_F") (pintype "bidirectional"))
      (node (ref "U102") (pin "5") (pinfunction "VOUT_5") (pintype "bidirectional"))
      (node (ref "U107") (pin "10") (pinfunction "P0B_10") (pintype "bidirectional"))
    )
    (net (code "40") (name "VOUT_1") (class "Default")
      (node (ref "C112") (pin "1") (pinfunction "1_1") (pintype "passive"))
      (node (ref "S101") (pin "H") (pinfunction "3_H") (pintype "bidirectional"))
      (node (ref "U103") (pin "5") (pinfunction "VOUT_5") (pintype "bidirectional"))
      (node (ref "U107") (pin "7") (pinfunction "P1B_7") (pintype "bidirectional"))
    )
    (net (code "41") (name "unconnected-(ICSP-A-Pad1)") (class "Default")
      (node (ref "ICSP-A") (pin "1") (pinfunction "1_1") (pintype "passive"))
    )
    (net (code "42") (name "unconnected-(ICSP-A-Pad6)") (class "Default")
      (node (ref "ICSP-A") (pin "6") (pinfunction "6_6") (pintype "passive"))
    )
    (net (code "43") (name "unconnected-(S102-NC-Pad3)") (class "Default")
      (node (ref "S102") (pin "3") (pinfunction "NC_3") (pintype "no_connect"))
    )
    (net (code "44") (name "unconnected-(S102-NC_2-Pad4)") (class "Default")
      (node (ref "S102") (pin "4") (pinfunction "NC_2_4") (pintype "no_connect"))
    )
    (net (code "45") (name "unconnected-(U108-PWRGD-Pad5)") (class "Default")
      (node (ref "U108") (pin "5") (pinfunction "PWRGD_5") (pintype "bidirectional"))
    )
    (net (code "46") (name "unconnected-(U109-INT1-Pad8)") (class "Default")
      (node (ref "U109") (pin "8") (pinfunction "INT1_8") (pintype "bidirectional"))
    )
    (net (code "47") (name "unconnected-(U109-INT2-Pad9)") (class "Default")
      (node (ref "U109") (pin "9") (pinfunction "INT2_9") (pintype "bidirectional"))
    )
    (net (code "48") (name "unconnected-(U109-NC-Pad3)") (class "Default")
      (node (ref "U109") (pin "3") (pinfunction "NC_3") (pintype "bidirectional"))
    )
    (net (code "49") (name "unconnected-(U109-N{slash}C-Pad11)") (class "Default")
      (node (ref "U109") (pin "11") (pinfunction "N/C_11") (pintype "bidirectional"))
    )
  )
)
